# DAU_Kupplung_1_phasig_V1_16.net
KiCad netlist of a schematic drawn in EAGLE
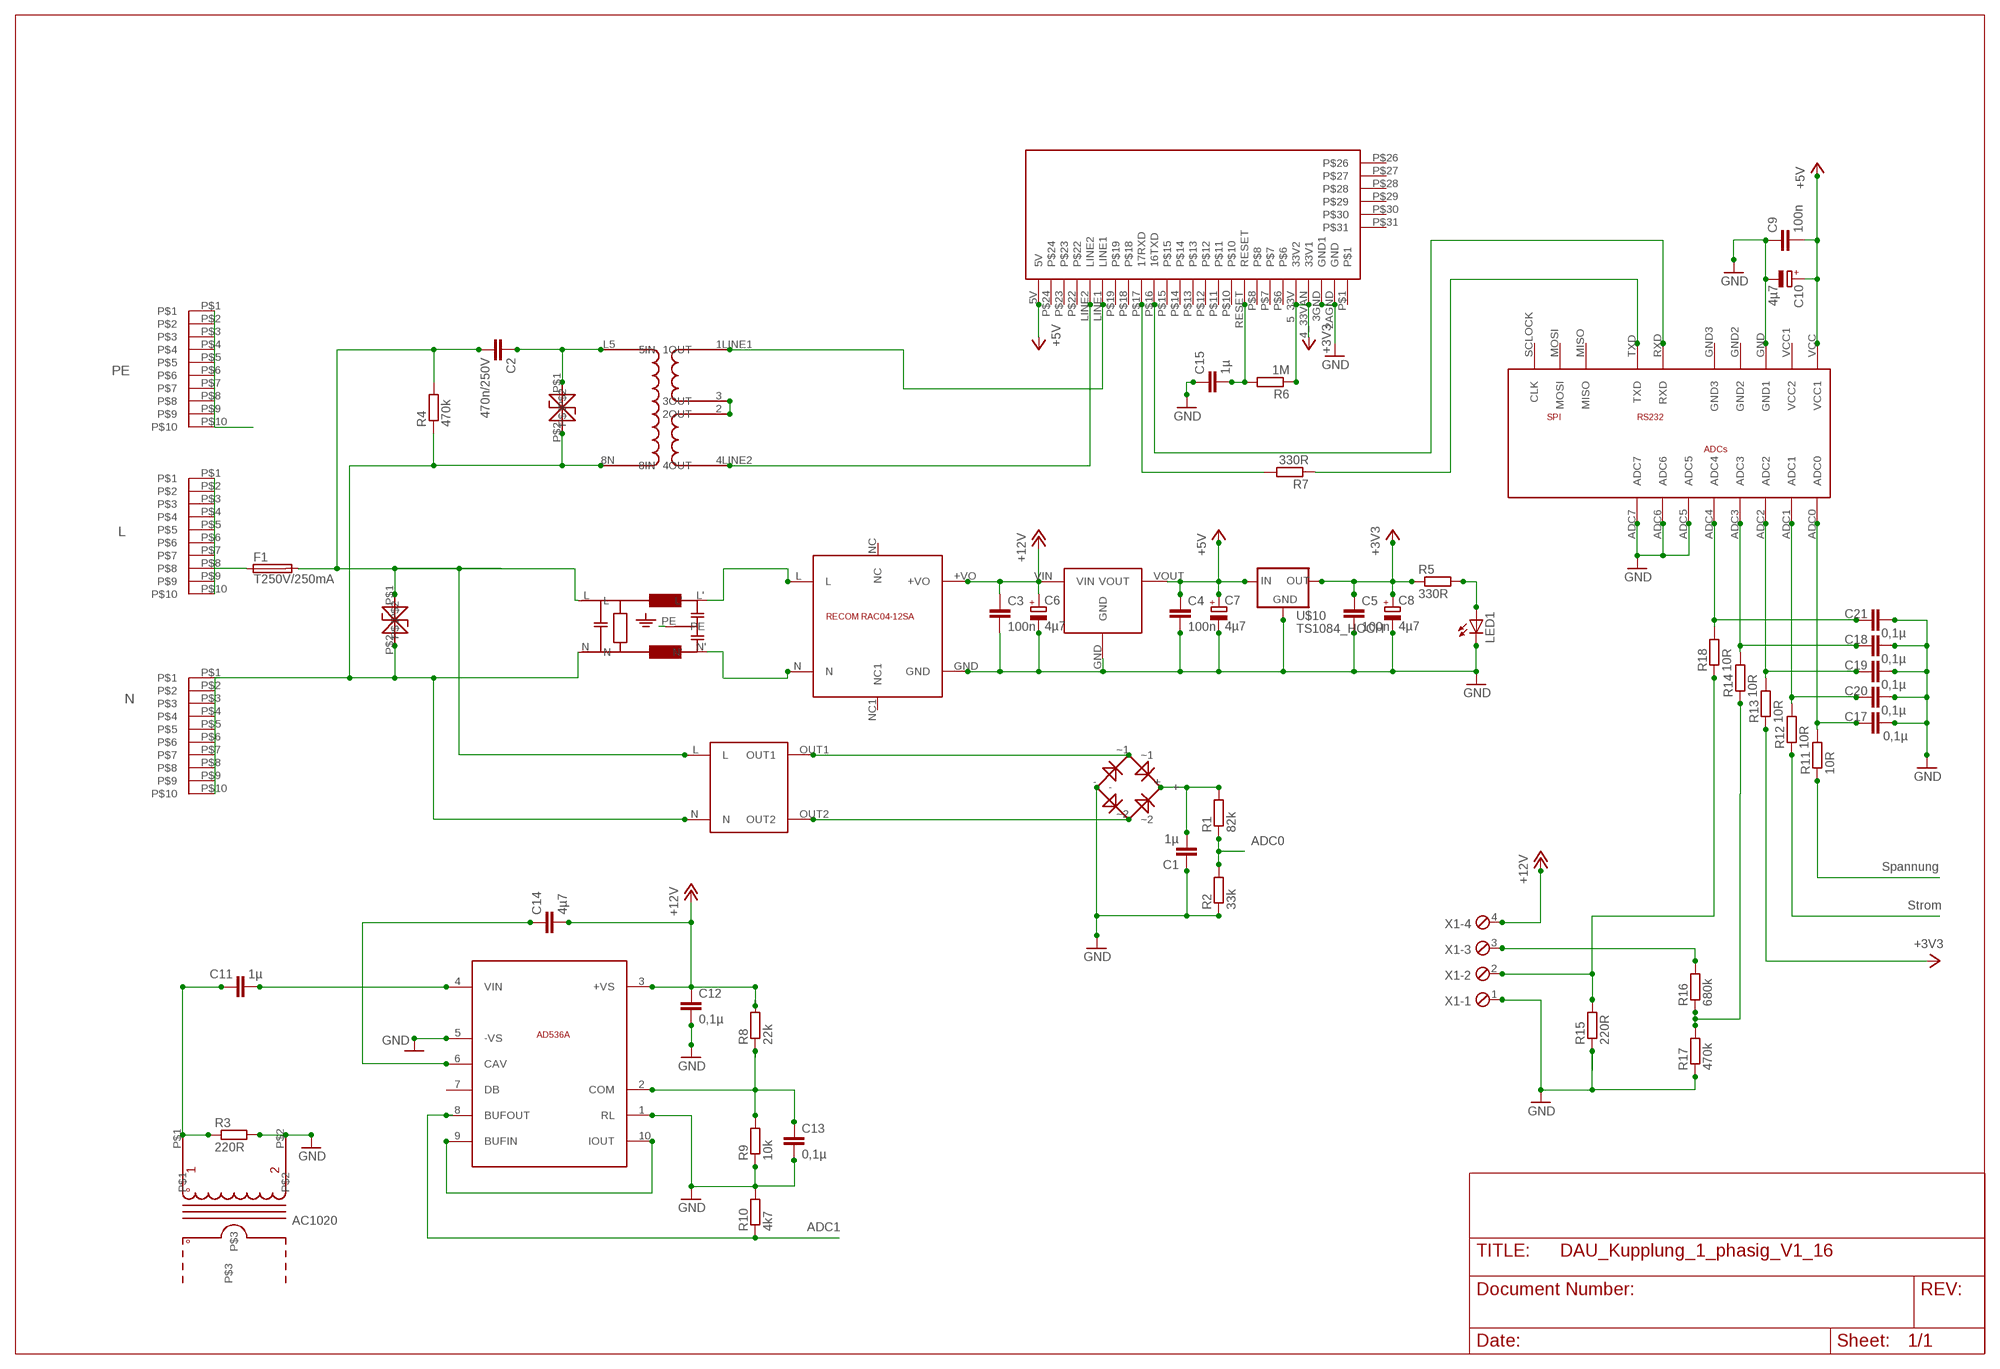
[diagram p0: schematic, sheet 1]

(export (version "E")
  (design (tool "Eeschema 10.0.6"))
  (components
    (comp (ref "AC1020")
      (value "AC1010")
      (footprint "eagle-import:AC1010")
      (libsource (lib "eagle-import") (part "AC1010"))
    )
    (comp (ref "C1")
      (value "1µ")
      (footprint "eagle-import:C2.5-3")
      (libsource (lib "eagle-import") (part "C2,5-3"))
    )
    (comp (ref "C2")
      (value "470n/250V")
      (footprint "eagle-import:C150-072X183")
      (libsource (lib "eagle-import") (part "resistor_C-EU150-072X183"))
    )
    (comp (ref "C3")
      (value "100n")
      (footprint "eagle-import:C0805")
      (libsource (lib "eagle-import") (part "resistor_C-EUC0805"))
    )
    (comp (ref "C4")
      (value "100n")
      (footprint "eagle-import:C0805")
      (libsource (lib "eagle-import") (part "resistor_C-EUC0805"))
    )
    (comp (ref "C5")
      (value "100n")
      (footprint "eagle-import:C0805")
      (libsource (lib "eagle-import") (part "resistor_C-EUC0805"))
    )
    (comp (ref "C6")
      (value "4µ7")
      (footprint "eagle-import:E2-4")
      (libsource (lib "eagle-import") (part "CPOL-EUE2-4"))
    )
    (comp (ref "C7")
      (value "4µ7")
      (footprint "eagle-import:E2-4")
      (libsource (lib "eagle-import") (part "CPOL-EUE2-4"))
    )
    (comp (ref "C8")
      (value "4µ7")
      (footprint "eagle-import:E2-4")
      (libsource (lib "eagle-import") (part "CPOL-EUE2-4"))
    )
    (comp (ref "C9")
      (value "100n")
      (footprint "eagle-import:C0805")
      (libsource (lib "eagle-import") (part "C-EUC0805"))
    )
    (comp (ref "C10")
      (value "4µ7")
      (footprint "eagle-import:E2-4")
      (libsource (lib "eagle-import") (part "CPOL-EUE2-4"))
    )
    (comp (ref "C11")
      (value "1µ")
      (footprint "eagle-import:C0805")
      (libsource (lib "eagle-import") (part "C-EUC0805"))
    )
    (comp (ref "C12")
      (value "0,1µ")
      (footprint "eagle-import:C0805")
      (libsource (lib "eagle-import") (part "C-EUC0805"))
    )
    (comp (ref "C13")
      (value "0,1µ")
      (footprint "eagle-import:C0805")
      (libsource (lib "eagle-import") (part "C-EUC0805"))
    )
    (comp (ref "C14")
      (value "4µ7")
      (footprint "eagle-import:C0805")
      (libsource (lib "eagle-import") (part "C-EUC0805"))
    )
    (comp (ref "C15")
      (value "1µ")
      (footprint "eagle-import:C0805")
      (libsource (lib "eagle-import") (part "resistor_C-EUC0805"))
    )
    (comp (ref "C17")
      (value "0,1µ")
      (footprint "eagle-import:C0805")
      (libsource (lib "eagle-import") (part "resistor_C-EUC0805"))
    )
    (comp (ref "C18")
      (value "0,1µ")
      (footprint "eagle-import:C0805")
      (libsource (lib "eagle-import") (part "resistor_C-EUC0805"))
    )
    (comp (ref "C19")
      (value "0,1µ")
      (footprint "eagle-import:C0805")
      (libsource (lib "eagle-import") (part "resistor_C-EUC0805"))
    )
    (comp (ref "C20")
      (value "0,1µ")
      (footprint "eagle-import:C0805")
      (libsource (lib "eagle-import") (part "resistor_C-EUC0805"))
    )
    (comp (ref "C21")
      (value "0,1µ")
      (footprint "eagle-import:C0805")
      (libsource (lib "eagle-import") (part "resistor_C-EUC0805"))
    )
    (comp (ref "F1")
      (value "T250V/250mA")
      (footprint "eagle-import:TR5")
      (libsource (lib "eagle-import") (part "TR5"))
    )
    (comp (ref "L")
      (value "PRINT_CONNECTOR")
      (footprint "eagle-import:FASTON_DOUBLE")
      (libsource (lib "eagle-import") (part "PRINT_CONNECTOR"))
    )
    (comp (ref "LED1")
      (value "LEDSQR2X5")
      (footprint "eagle-import:LED2X5")
      (libsource (lib "eagle-import") (part "LEDSQR2X5"))
    )
    (comp (ref "N")
      (value "PRINT_CONNECTOR")
      (footprint "eagle-import:FASTON_DOUBLE")
      (libsource (lib "eagle-import") (part "PRINT_CONNECTOR"))
    )
    (comp (ref "PE")
      (value "PRINT_CONNECTOR")
      (footprint "eagle-import:FASTON_DOUBLE")
      (libsource (lib "eagle-import") (part "PRINT_CONNECTOR"))
    )
    (comp (ref "R1")
      (value "82k")
      (footprint "eagle-import:R1206")
      (libsource (lib "eagle-import") (part "R-EU_R1206"))
    )
    (comp (ref "R2")
      (value "33k")
      (footprint "eagle-import:R1206")
      (libsource (lib "eagle-import") (part "R-EU_R1206"))
    )
    (comp (ref "R3")
      (value "220R")
      (footprint "eagle-import:R1206")
      (libsource (lib "eagle-import") (part "R-EU_R1206"))
    )
    (comp (ref "R4")
      (value "470k")
      (footprint "eagle-import:0204_7")
      (libsource (lib "eagle-import") (part "R-EU_0204/7"))
    )
    (comp (ref "R5")
      (value "330R")
      (footprint "eagle-import:R1206")
      (libsource (lib "eagle-import") (part "R-EU_R1206"))
    )
    (comp (ref "R6")
      (value "1M")
      (footprint "eagle-import:R1206")
      (libsource (lib "eagle-import") (part "R-EU_R1206"))
    )
    (comp (ref "R7")
      (value "330R")
      (footprint "eagle-import:R1206")
      (libsource (lib "eagle-import") (part "R-EU_R1206"))
    )
    (comp (ref "R8")
      (value "22k")
      (footprint "eagle-import:R1206")
      (libsource (lib "eagle-import") (part "R-EU_R1206"))
    )
    (comp (ref "R9")
      (value "10k")
      (footprint "eagle-import:R1206")
      (libsource (lib "eagle-import") (part "R-EU_R1206"))
    )
    (comp (ref "R10")
      (value "4k7")
      (footprint "eagle-import:R1206")
      (libsource (lib "eagle-import") (part "R-EU_R1206"))
    )
    (comp (ref "R11")
      (value "10R")
      (footprint "eagle-import:R1206")
      (libsource (lib "eagle-import") (part "R-EU_R1206"))
    )
    (comp (ref "R12")
      (value "10R")
      (footprint "eagle-import:R1206")
      (libsource (lib "eagle-import") (part "R-EU_R1206"))
    )
    (comp (ref "R13")
      (value "10R")
      (footprint "eagle-import:R1206")
      (libsource (lib "eagle-import") (part "R-EU_R1206"))
    )
    (comp (ref "R14")
      (value "10R")
      (footprint "eagle-import:R1206")
      (libsource (lib "eagle-import") (part "R-EU_R1206"))
    )
    (comp (ref "R15")
      (value "220R")
      (footprint "eagle-import:R1206")
      (libsource (lib "eagle-import") (part "R-EU_R1206"))
    )
    (comp (ref "R16")
      (value "680k")
      (footprint "eagle-import:R1206")
      (libsource (lib "eagle-import") (part "R-EU_R1206"))
    )
    (comp (ref "R17")
      (value "470k")
      (footprint "eagle-import:R1206")
      (libsource (lib "eagle-import") (part "R-EU_R1206"))
    )
    (comp (ref "R18")
      (value "10R")
      (footprint "eagle-import:R1206")
      (libsource (lib "eagle-import") (part "R-EU_R1206"))
    )
    (comp (ref "U$1")
      (value "RECOM_RAC04_12SA")
      (footprint "eagle-import:RAC04_12SA")
      (libsource (lib "eagle-import") (part "RECOM_RAC04_12SA"))
    )
    (comp (ref "U$2")
      (value "SICHERHEITSTRAFO")
      (footprint "eagle-import:TRAFO_0,35VA")
      (libsource (lib "eagle-import") (part "SICHERHEITSTRAFO"))
    )
    (comp (ref "U$3")
      (value "ADUC831_MINIMUM")
      (footprint "eagle-import:ADUC_MINIMUM")
      (libsource (lib "eagle-import") (part "ADUC831_MINIMUM"))
    )
    (comp (ref "U$4")
      (value "IT800")
      (footprint "eagle-import:IT800")
      (libsource (lib "eagle-import") (part "IT800"))
    )
    (comp (ref "U$5")
      (value "PLC_UEBERTRAGER_V2")
      (footprint "eagle-import:PLC-UEBERTRAGER_V2")
      (libsource (lib "eagle-import") (part "PLC_UEBERTRAGER_V2"))
    )
    (comp (ref "U$6")
      (value "NETZFILTER_05_A")
      (footprint "eagle-import:NETZFILTER")
      (libsource (lib "eagle-import") (part "NETZFILTER_05_A"))
    )
    (comp (ref "U$7")
      (value "AD536")
      (footprint "eagle-import:TO100_10PIN")
      (libsource (lib "eagle-import") (part "AD536"))
    )
    (comp (ref "U$8")
      (value "RECTIFIER")
      (footprint "eagle-import:RECTIFIER")
      (libsource (lib "eagle-import") (part "RECTIFIER"))
    )
    (comp (ref "U$9")
      (value "TSV")
      (footprint "eagle-import:TSV")
      (libsource (lib "eagle-import") (part "TSV"))
    )
    (comp (ref "U$10")
      (value "TS1084_HOCH")
      (footprint "eagle-import:TS1084_HOCH")
      (libsource (lib "eagle-import") (part "TS1084_HOCH"))
    )
    (comp (ref "U$11")
      (value "RECOM_785_05")
      (footprint "eagle-import:RECOM785X")
      (libsource (lib "eagle-import") (part "RECOM_785_05"))
    )
    (comp (ref "U$12")
      (value "TSV")
      (footprint "eagle-import:TSV")
      (libsource (lib "eagle-import") (part "TSV"))
    )
    (comp (ref "X1")
      (value "MPT4")
      (footprint "eagle-import:4POL254")
      (libsource (lib "eagle-import") (part "MPT4"))
    )
  )
  (nets
    (net (code "1") (name "+3V3") (class "Default")
      (node (ref "C5") (pin "1") (pinfunction "1_1") (pintype "passive"))
      (node (ref "C8") (pin "+") (pinfunction "+_+") (pintype "passive"))
      (node (ref "R13") (pin "1") (pinfunction "1_1") (pintype "passive"))
      (node (ref "R5") (pin "1") (pinfunction "1_1") (pintype "passive"))
      (node (ref "R6") (pin "1") (pinfunction "1_1") (pintype "passive"))
      (node (ref "U$10") (pin "OUT") (pinfunction "OUT_OUT") (pintype "passive"))
      (node (ref "U$4") (pin "4_33VAN") (pinfunction "33V1_4_33VAN") (pintype "bidirectional"))
      (node (ref "U$4") (pin "5_33V") (pinfunction "33V2_5_33V") (pintype "bidirectional"))
    )
    (net (code "2") (name "+5V") (class "Default")
      (node (ref "C10") (pin "+") (pinfunction "+_+") (pintype "passive"))
      (node (ref "C4") (pin "1") (pinfunction "1_1") (pintype "passive"))
      (node (ref "C7") (pin "+") (pinfunction "+_+") (pintype "passive"))
      (node (ref "C9") (pin "2") (pinfunction "2_2") (pintype "passive"))
      (node (ref "U$10") (pin "IN") (pinfunction "IN_IN") (pintype "input"))
      (node (ref "U$11") (pin "VOUT") (pinfunction "VOUT_VOUT") (pintype "bidirectional"))
      (node (ref "U$3") (pin "VCC") (pinfunction "VCC1_VCC") (pintype "bidirectional"))
      (node (ref "U$4") (pin "5V") (pinfunction "5V_5V") (pintype "bidirectional"))
    )
    (net (code "3") (name "+12V") (class "Default")
      (node (ref "C12") (pin "1") (pinfunction "1_1") (pintype "passive"))
      (node (ref "C14") (pin "2") (pinfunction "2_2") (pintype "passive"))
      (node (ref "C3") (pin "1") (pinfunction "1_1") (pintype "passive"))
      (node (ref "C6") (pin "+") (pinfunction "+_+") (pintype "passive"))
      (node (ref "R8") (pin "2") (pinfunction "2_2") (pintype "passive"))
      (node (ref "U$1") (pin "+VO") (pinfunction "+VO_+VO") (pintype "bidirectional"))
      (node (ref "U$11") (pin "VIN") (pinfunction "VIN_VIN") (pintype "bidirectional"))
      (node (ref "U$7") (pin "3") (pinfunction "+VS_3") (pintype "bidirectional"))
      (node (ref "X1") (pin "4") (pinfunction "1_4") (pintype "passive"))
    )
    (net (code "4") (name "/ADC0") (class "Default")
      (node (ref "R1") (pin "1") (pinfunction "1_1") (pintype "passive"))
      (node (ref "R11") (pin "1") (pinfunction "1_1") (pintype "passive"))
      (node (ref "R2") (pin "2") (pinfunction "2_2") (pintype "passive"))
    )
    (net (code "5") (name "/ADC1") (class "Default")
      (node (ref "R10") (pin "1") (pinfunction "1_1") (pintype "passive"))
      (node (ref "R12") (pin "1") (pinfunction "1_1") (pintype "passive"))
      (node (ref "U$7") (pin "8") (pinfunction "BUFOUT_8") (pintype "bidirectional"))
    )
    (net (code "6") (name "/PE") (class "Default")
      (node (ref "PE") (pin "P$1") (pinfunction "P$1_P$1") (pintype "bidirectional"))
      (node (ref "PE") (pin "P$10") (pinfunction "P$10_P$10") (pintype "bidirectional"))
      (node (ref "PE") (pin "P$2") (pinfunction "P$2_P$2") (pintype "bidirectional"))
      (node (ref "PE") (pin "P$3") (pinfunction "P$3_P$3") (pintype "bidirectional"))
      (node (ref "PE") (pin "P$4") (pinfunction "P$4_P$4") (pintype "bidirectional"))
      (node (ref "PE") (pin "P$5") (pinfunction "P$5_P$5") (pintype "bidirectional"))
      (node (ref "PE") (pin "P$6") (pinfunction "P$6_P$6") (pintype "bidirectional"))
      (node (ref "PE") (pin "P$7") (pinfunction "P$7_P$7") (pintype "bidirectional"))
      (node (ref "PE") (pin "P$8") (pinfunction "P$8_P$8") (pintype "bidirectional"))
      (node (ref "PE") (pin "P$9") (pinfunction "P$9_P$9") (pintype "bidirectional"))
      (node (ref "U$6") (pin "PE") (pinfunction "PE_PE") (pintype "input"))
    )
    (net (code "7") (name "GND") (class "Default")
      (node (ref "AC1020") (pin "P$2") (pinfunction "P$2_P$2") (pintype "bidirectional"))
      (node (ref "C1") (pin "1") (pinfunction "1_1") (pintype "passive"))
      (node (ref "C10") (pin "-") (pinfunction "-_-") (pintype "passive"))
      (node (ref "C12") (pin "2") (pinfunction "2_2") (pintype "passive"))
      (node (ref "C13") (pin "2") (pinfunction "2_2") (pintype "passive"))
      (node (ref "C15") (pin "1") (pinfunction "1_1") (pintype "passive"))
      (node (ref "C17") (pin "2") (pinfunction "2_2") (pintype "passive"))
      (node (ref "C18") (pin "2") (pinfunction "2_2") (pintype "passive"))
      (node (ref "C19") (pin "2") (pinfunction "2_2") (pintype "passive"))
      (node (ref "C20") (pin "2") (pinfunction "2_2") (pintype "passive"))
      (node (ref "C21") (pin "2") (pinfunction "2_2") (pintype "passive"))
      (node (ref "C3") (pin "2") (pinfunction "2_2") (pintype "passive"))
      (node (ref "C4") (pin "2") (pinfunction "2_2") (pintype "passive"))
      (node (ref "C5") (pin "2") (pinfunction "2_2") (pintype "passive"))
      (node (ref "C6") (pin "-") (pinfunction "-_-") (pintype "passive"))
      (node (ref "C7") (pin "-") (pinfunction "-_-") (pintype "passive"))
      (node (ref "C8") (pin "-") (pinfunction "-_-") (pintype "passive"))
      (node (ref "C9") (pin "1") (pinfunction "1_1") (pintype "passive"))
      (node (ref "LED1") (pin "K") (pinfunction "C_K") (pintype "passive"))
      (node (ref "R10") (pin "2") (pinfunction "2_2") (pintype "passive"))
      (node (ref "R15") (pin "1") (pinfunction "1_1") (pintype "passive"))
      (node (ref "R17") (pin "1") (pinfunction "1_1") (pintype "passive"))
      (node (ref "R2") (pin "1") (pinfunction "1_1") (pintype "passive"))
      (node (ref "R3") (pin "2") (pinfunction "2_2") (pintype "passive"))
      (node (ref "R9") (pin "1") (pinfunction "1_1") (pintype "passive"))
      (node (ref "U$1") (pin "GND") (pinfunction "GND_GND") (pintype "bidirectional"))
      (node (ref "U$10") (pin "GND") (pinfunction "GND_GND") (pintype "input"))
      (node (ref "U$11") (pin "GND") (pinfunction "GND_GND") (pintype "bidirectional"))
      (node (ref "U$3") (pin "ADC5") (pinfunction "ADC5_ADC5") (pintype "bidirectional"))
      (node (ref "U$3") (pin "ADC6") (pinfunction "ADC6_ADC6") (pintype "bidirectional"))
      (node (ref "U$3") (pin "ADC7") (pinfunction "ADC7_ADC7") (pintype "bidirectional"))
      (node (ref "U$3") (pin "GND") (pinfunction "GND1_GND") (pintype "bidirectional"))
      (node (ref "U$4") (pin "2AGND") (pinfunction "GND_2AGND") (pintype "bidirectional"))
      (node (ref "U$4") (pin "3GND") (pinfunction "GND1_3GND") (pintype "bidirectional"))
      (node (ref "U$7") (pin "1") (pinfunction "RL_1") (pintype "bidirectional"))
      (node (ref "U$7") (pin "5") (pinfunction "-VS_5") (pintype "bidirectional"))
      (node (ref "U$8") (pin "-") (pinfunction "-_-") (pintype "bidirectional"))
      (node (ref "X1") (pin "1") (pinfunction "1_1") (pintype "passive"))
    )
    (net (code "8") (name "Net-(AC1020-PadP$1)") (class "Default")
      (node (ref "AC1020") (pin "P$1") (pinfunction "P$1_P$1") (pintype "bidirectional"))
      (node (ref "C11") (pin "1") (pinfunction "1_1") (pintype "passive"))
      (node (ref "R3") (pin "1") (pinfunction "1_1") (pintype "passive"))
    )
    (net (code "9") (name "Net-(C1-Pad2)") (class "Default")
      (node (ref "C1") (pin "2") (pinfunction "2_2") (pintype "passive"))
      (node (ref "R1") (pin "2") (pinfunction "2_2") (pintype "passive"))
      (node (ref "U$8") (pin "+") (pinfunction "+_+") (pintype "bidirectional"))
    )
    (net (code "10") (name "Net-(C2-Pad2)") (class "Default")
      (node (ref "C2") (pin "2") (pinfunction "2_2") (pintype "passive"))
      (node (ref "F1") (pin "2") (pinfunction "2_2") (pintype "passive"))
      (node (ref "R4") (pin "2") (pinfunction "2_2") (pintype "passive"))
      (node (ref "U$2") (pin "L") (pinfunction "L_L") (pintype "bidirectional"))
      (node (ref "U$6") (pin "L") (pinfunction "L_L") (pintype "bidirectional"))
      (node (ref "U$9") (pin "P$1") (pinfunction "P$1_P$1") (pintype "bidirectional"))
    )
    (net (code "11") (name "Net-(C15-Pad2)") (class "Default")
      (node (ref "C15") (pin "2") (pinfunction "2_2") (pintype "passive"))
      (node (ref "R6") (pin "2") (pinfunction "2_2") (pintype "passive"))
      (node (ref "U$4") (pin "RESET") (pinfunction "RESET_RESET") (pintype "bidirectional"))
    )
    (net (code "12") (name "Net-(C17-Pad1)") (class "Default")
      (node (ref "C17") (pin "1") (pinfunction "1_1") (pintype "passive"))
      (node (ref "R11") (pin "2") (pinfunction "2_2") (pintype "passive"))
      (node (ref "U$3") (pin "ADC0") (pinfunction "ADC0_ADC0") (pintype "bidirectional"))
    )
    (net (code "13") (name "Net-(C18-Pad1)") (class "Default")
      (node (ref "C18") (pin "1") (pinfunction "1_1") (pintype "passive"))
      (node (ref "R14") (pin "2") (pinfunction "2_2") (pintype "passive"))
      (node (ref "U$3") (pin "ADC3") (pinfunction "ADC3_ADC3") (pintype "bidirectional"))
    )
    (net (code "14") (name "Net-(C19-Pad1)") (class "Default")
      (node (ref "C19") (pin "1") (pinfunction "1_1") (pintype "passive"))
      (node (ref "R13") (pin "2") (pinfunction "2_2") (pintype "passive"))
      (node (ref "U$3") (pin "ADC2") (pinfunction "ADC2_ADC2") (pintype "bidirectional"))
    )
    (net (code "15") (name "Net-(C20-Pad1)") (class "Default")
      (node (ref "C20") (pin "1") (pinfunction "1_1") (pintype "passive"))
      (node (ref "R12") (pin "2") (pinfunction "2_2") (pintype "passive"))
      (node (ref "U$3") (pin "ADC1") (pinfunction "ADC1_ADC1") (pintype "bidirectional"))
    )
    (net (code "16") (name "Net-(C21-Pad1)") (class "Default")
      (node (ref "C21") (pin "1") (pinfunction "1_1") (pintype "passive"))
      (node (ref "R18") (pin "2") (pinfunction "2_2") (pintype "passive"))
      (node (ref "U$3") (pin "ADC4") (pinfunction "ADC4_ADC4") (pintype "bidirectional"))
    )
    (net (code "17") (name "Net-(F1-Pad1)") (class "Default")
      (node (ref "F1") (pin "1") (pinfunction "1_1") (pintype "passive"))
      (node (ref "L") (pin "P$1") (pinfunction "P$1_P$1") (pintype "bidirectional"))
      (node (ref "L") (pin "P$10") (pinfunction "P$10_P$10") (pintype "bidirectional"))
      (node (ref "L") (pin "P$2") (pinfunction "P$2_P$2") (pintype "bidirectional"))
      (node (ref "L") (pin "P$3") (pinfunction "P$3_P$3") (pintype "bidirectional"))
      (node (ref "L") (pin "P$4") (pinfunction "P$4_P$4") (pintype "bidirectional"))
      (node (ref "L") (pin "P$5") (pinfunction "P$5_P$5") (pintype "bidirectional"))
      (node (ref "L") (pin "P$6") (pinfunction "P$6_P$6") (pintype "bidirectional"))
      (node (ref "L") (pin "P$7") (pinfunction "P$7_P$7") (pintype "bidirectional"))
      (node (ref "L") (pin "P$8") (pinfunction "P$8_P$8") (pintype "bidirectional"))
      (node (ref "L") (pin "P$9") (pinfunction "P$9_P$9") (pintype "bidirectional"))
    )
    (net (code "18") (name "Net-(LED1-PadA)") (class "Default")
      (node (ref "LED1") (pin "A") (pinfunction "A_A") (pintype "passive"))
      (node (ref "R5") (pin "2") (pinfunction "2_2") (pintype "passive"))
    )
    (net (code "19") (name "Net-(R7-Pad1)") (class "Default")
      (node (ref "R7") (pin "1") (pinfunction "1_1") (pintype "passive"))
      (node (ref "U$3") (pin "TXD") (pinfunction "TXD_TXD") (pintype "bidirectional"))
    )
    (net (code "20") (name "Net-(R14-Pad1)") (class "Default")
      (node (ref "R14") (pin "1") (pinfunction "1_1") (pintype "passive"))
      (node (ref "R16") (pin "1") (pinfunction "1_1") (pintype "passive"))
      (node (ref "R17") (pin "2") (pinfunction "2_2") (pintype "passive"))
    )
    (net (code "21") (name "Net-(U$1-PadL)") (class "Default")
      (node (ref "U$1") (pin "L") (pinfunction "L_L") (pintype "bidirectional"))
      (node (ref "U$6") (pin "L'") (pinfunction "L'_L'") (pintype "bidirectional"))
    )
    (net (code "22") (name "Net-(U$1-PadN)") (class "Default")
      (node (ref "U$1") (pin "N") (pinfunction "N_N") (pintype "bidirectional"))
      (node (ref "U$6") (pin "N'") (pinfunction "N'_N'") (pintype "bidirectional"))
    )
    (net (code "23") (name "Net-(U$4-16TXD)") (class "Default")
      (node (ref "U$3") (pin "RXD") (pinfunction "RXD_RXD") (pintype "bidirectional"))
      (node (ref "U$4") (pin "P$16") (pinfunction "16TXD_P$16") (pintype "bidirectional"))
    )
    (net (code "24") (name "Net-(U$4-17RXD)") (class "Default")
      (node (ref "R7") (pin "2") (pinfunction "2_2") (pintype "passive"))
      (node (ref "U$4") (pin "P$17") (pinfunction "17RXD_P$17") (pintype "bidirectional"))
    )
    (net (code "25") (name "Net-(U$5-1OUT)") (class "Default")
      (node (ref "U$4") (pin "LINE1") (pinfunction "LINE1_LINE1") (pintype "bidirectional"))
      (node (ref "U$5") (pin "1LINE1") (pinfunction "1OUT_1LINE1") (pintype "output"))
    )
    (net (code "26") (name "Net-(U$5-2OUT)") (class "Default")
      (node (ref "U$5") (pin "2") (pinfunction "2OUT_2") (pintype "output"))
      (node (ref "U$5") (pin "3") (pinfunction "3OUT_3") (pintype "output"))
    )
    (net (code "27") (name "Net-(U$5-4OUT)") (class "Default")
      (node (ref "U$4") (pin "LINE2") (pinfunction "LINE2_LINE2") (pintype "bidirectional"))
      (node (ref "U$5") (pin "4LINE2") (pinfunction "4OUT_4LINE2") (pintype "output"))
    )
    (net (code "28") (name "Net-(U$5-5IN)") (class "Default")
      (node (ref "C2") (pin "1") (pinfunction "1_1") (pintype "passive"))
      (node (ref "U$12") (pin "P$1") (pinfunction "P$1_P$1") (pintype "bidirectional"))
      (node (ref "U$5") (pin "L5") (pinfunction "5IN_L5") (pintype "input"))
    )
    (net (code "29") (name "Net-(U$5-8IN)") (class "Default")
      (node (ref "N") (pin "P$1") (pinfunction "P$1_P$1") (pintype "bidirectional"))
      (node (ref "N") (pin "P$10") (pinfunction "P$10_P$10") (pintype "bidirectional"))
      (node (ref "N") (pin "P$2") (pinfunction "P$2_P$2") (pintype "bidirectional"))
      (node (ref "N") (pin "P$3") (pinfunction "P$3_P$3") (pintype "bidirectional"))
      (node (ref "N") (pin "P$4") (pinfunction "P$4_P$4") (pintype "bidirectional"))
      (node (ref "N") (pin "P$5") (pinfunction "P$5_P$5") (pintype "bidirectional"))
      (node (ref "N") (pin "P$6") (pinfunction "P$6_P$6") (pintype "bidirectional"))
      (node (ref "N") (pin "P$7") (pinfunction "P$7_P$7") (pintype "bidirectional"))
      (node (ref "N") (pin "P$8") (pinfunction "P$8_P$8") (pintype "bidirectional"))
      (node (ref "N") (pin "P$9") (pinfunction "P$9_P$9") (pintype "bidirectional"))
      (node (ref "R4") (pin "1") (pinfunction "1_1") (pintype "passive"))
      (node (ref "U$12") (pin "P$2") (pinfunction "P$2_P$2") (pintype "bidirectional"))
      (node (ref "U$2") (pin "N") (pinfunction "N_N") (pintype "bidirectional"))
      (node (ref "U$5") (pin "8N") (pinfunction "8IN_8N") (pintype "input"))
      (node (ref "U$6") (pin "N") (pinfunction "N_N") (pintype "bidirectional"))
      (node (ref "U$9") (pin "P$2") (pinfunction "P$2_P$2") (pintype "bidirectional"))
    )
    (net (code "30") (name "Net-(U$7-BUFIN)") (class "Default")
      (node (ref "U$7") (pin "10") (pinfunction "IOUT_10") (pintype "bidirectional"))
      (node (ref "U$7") (pin "9") (pinfunction "BUFIN_9") (pintype "bidirectional"))
    )
    (net (code "31") (name "Net-(U$7-CAV)") (class "Default")
      (node (ref "C14") (pin "1") (pinfunction "1_1") (pintype "passive"))
      (node (ref "U$7") (pin "6") (pinfunction "CAV_6") (pintype "bidirectional"))
    )
    (net (code "32") (name "Net-(U$7-COM)") (class "Default")
      (node (ref "C13") (pin "1") (pinfunction "1_1") (pintype "passive"))
      (node (ref "R8") (pin "1") (pinfunction "1_1") (pintype "passive"))
      (node (ref "R9") (pin "2") (pinfunction "2_2") (pintype "passive"))
      (node (ref "U$7") (pin "2") (pinfunction "COM_2") (pintype "bidirectional"))
    )
    (net (code "33") (name "Net-(U$7-VIN)") (class "Default")
      (node (ref "C11") (pin "2") (pinfunction "2_2") (pintype "passive"))
      (node (ref "U$7") (pin "4") (pinfunction "VIN_4") (pintype "bidirectional"))
    )
    (net (code "34") (name "Net-(U$8-~{1})") (class "Default")
      (node (ref "U$2") (pin "OUT1") (pinfunction "OUT1_OUT1") (pintype "bidirectional"))
      (node (ref "U$8") (pin "~1") (pinfunction "~{1}_~1") (pintype "bidirectional"))
    )
    (net (code "35") (name "Net-(U$8-~{2})") (class "Default")
      (node (ref "U$2") (pin "OUT2") (pinfunction "OUT2_OUT2") (pintype "bidirectional"))
      (node (ref "U$8") (pin "~2") (pinfunction "~{2}_~2") (pintype "bidirectional"))
    )
    (net (code "36") (name "Net-(X1B-1)") (class "Default")
      (node (ref "R15") (pin "2") (pinfunction "2_2") (pintype "passive"))
      (node (ref "R18") (pin "1") (pinfunction "1_1") (pintype "passive"))
      (node (ref "X1") (pin "2") (pinfunction "1_2") (pintype "passive"))
    )
    (net (code "37") (name "Net-(X1C-1)") (class "Default")
      (node (ref "R16") (pin "2") (pinfunction "2_2") (pintype "passive"))
      (node (ref "X1") (pin "3") (pinfunction "1_3") (pintype "passive"))
    )
    (net (code "38") (name "unconnected-(AC1020-PadP$3)") (class "Default")
      (node (ref "AC1020") (pin "P$3") (pinfunction "P$3_P$3") (pintype "bidirectional"))
    )
    (net (code "39") (name "unconnected-(U$1-PadNC)") (class "Default")
      (node (ref "U$1") (pin "NC") (pinfunction "NC_NC") (pintype "bidirectional"))
    )
    (net (code "40") (name "unconnected-(U$1-PadNC1)") (class "Default")
      (node (ref "U$1") (pin "NC1") (pinfunction "NC1_NC1") (pintype "bidirectional"))
    )
    (net (code "41") (name "unconnected-(U$3-CLK-PadSCLOCK)") (class "Default")
      (node (ref "U$3") (pin "SCLOCK") (pinfunction "CLK_SCLOCK") (pintype "bidirectional"))
    )
    (net (code "42") (name "unconnected-(U$3-PadGND2)") (class "Default")
      (node (ref "U$3") (pin "GND2") (pinfunction "GND2_GND2") (pintype "bidirectional"))
    )
    (net (code "43") (name "unconnected-(U$3-PadGND3)") (class "Default")
      (node (ref "U$3") (pin "GND3") (pinfunction "GND3_GND3") (pintype "bidirectional"))
    )
    (net (code "44") (name "unconnected-(U$3-PadMISO)") (class "Default")
      (node (ref "U$3") (pin "MISO") (pinfunction "MISO_MISO") (pintype "bidirectional"))
    )
    (net (code "45") (name "unconnected-(U$3-PadMOSI)") (class "Default")
      (node (ref "U$3") (pin "MOSI") (pinfunction "MOSI_MOSI") (pintype "bidirectional"))
    )
    (net (code "46") (name "unconnected-(U$3-VCC2-PadVCC1)") (class "Default")
      (node (ref "U$3") (pin "VCC1") (pinfunction "VCC2_VCC1") (pintype "bidirectional"))
    )
    (net (code "47") (name "unconnected-(U$4-PadP$1)") (class "Default")
      (node (ref "U$4") (pin "P$1") (pinfunction "P$1_P$1") (pintype "bidirectional"))
    )
    (net (code "48") (name "unconnected-(U$4-PadP$6)") (class "Default")
      (node (ref "U$4") (pin "P$6") (pinfunction "P$6_P$6") (pintype "bidirectional"))
    )
    (net (code "49") (name "unconnected-(U$4-PadP$7)") (class "Default")
      (node (ref "U$4") (pin "P$7") (pinfunction "P$7_P$7") (pintype "bidirectional"))
    )
    (net (code "50") (name "unconnected-(U$4-PadP$8)") (class "Default")
      (node (ref "U$4") (pin "P$8") (pinfunction "P$8_P$8") (pintype "bidirectional"))
    )
    (net (code "51") (name "unconnected-(U$4-PadP$10)") (class "Default")
      (node (ref "U$4") (pin "P$10") (pinfunction "P$10_P$10") (pintype "bidirectional"))
    )
    (net (code "52") (name "unconnected-(U$4-PadP$11)") (class "Default")
      (node (ref "U$4") (pin "P$11") (pinfunction "P$11_P$11") (pintype "bidirectional"))
    )
    (net (code "53") (name "unconnected-(U$4-PadP$12)") (class "Default")
      (node (ref "U$4") (pin "P$12") (pinfunction "P$12_P$12") (pintype "bidirectional"))
    )
    (net (code "54") (name "unconnected-(U$4-PadP$13)") (class "Default")
      (node (ref "U$4") (pin "P$13") (pinfunction "P$13_P$13") (pintype "bidirectional"))
    )
    (net (code "55") (name "unconnected-(U$4-PadP$14)") (class "Default")
      (node (ref "U$4") (pin "P$14") (pinfunction "P$14_P$14") (pintype "bidirectional"))
    )
    (net (code "56") (name "unconnected-(U$4-PadP$15)") (class "Default")
      (node (ref "U$4") (pin "P$15") (pinfunction "P$15_P$15") (pintype "bidirectional"))
    )
    (net (code "57") (name "unconnected-(U$4-PadP$18)") (class "Default")
      (node (ref "U$4") (pin "P$18") (pinfunction "P$18_P$18") (pintype "bidirectional"))
    )
    (net (code "58") (name "unconnected-(U$4-PadP$19)") (class "Default")
      (node (ref "U$4") (pin "P$19") (pinfunction "P$19_P$19") (pintype "bidirectional"))
    )
    (net (code "59") (name "unconnected-(U$4-PadP$22)") (class "Default")
      (node (ref "U$4") (pin "P$22") (pinfunction "P$22_P$22") (pintype "bidirectional"))
    )
    (net (code "60") (name "unconnected-(U$4-PadP$23)") (class "Default")
      (node (ref "U$4") (pin "P$23") (pinfunction "P$23_P$23") (pintype "bidirectional"))
    )
    (net (code "61") (name "unconnected-(U$4-PadP$24)") (class "Default")
      (node (ref "U$4") (pin "P$24") (pinfunction "P$24_P$24") (pintype "bidirectional"))
    )
    (net (code "62") (name "unconnected-(U$4-PadP$26)") (class "Default")
      (node (ref "U$4") (pin "P$26") (pinfunction "P$26_P$26") (pintype "bidirectional"))
    )
    (net (code "63") (name "unconnected-(U$4-PadP$27)") (class "Default")
      (node (ref "U$4") (pin "P$27") (pinfunction "P$27_P$27") (pintype "bidirectional"))
    )
    (net (code "64") (name "unconnected-(U$4-PadP$28)") (class "Default")
      (node (ref "U$4") (pin "P$28") (pinfunction "P$28_P$28") (pintype "bidirectional"))
    )
    (net (code "65") (name "unconnected-(U$4-PadP$29)") (class "Default")
      (node (ref "U$4") (pin "P$29") (pinfunction "P$29_P$29") (pintype "bidirectional"))
    )
    (net (code "66") (name "unconnected-(U$4-PadP$30)") (class "Default")
      (node (ref "U$4") (pin "P$30") (pinfunction "P$30_P$30") (pintype "bidirectional"))
    )
    (net (code "67") (name "unconnected-(U$4-PadP$31)") (class "Default")
      (node (ref "U$4") (pin "P$31") (pinfunction "P$31_P$31") (pintype "bidirectional"))
    )
    (net (code "68") (name "unconnected-(U$7-DB-Pad7)") (class "Default")
      (node (ref "U$7") (pin "7") (pinfunction "DB_7") (pintype "bidirectional"))
    )
  )
)
